# backplane.net
KiCad netlist of a schematic drawn in EAGLE
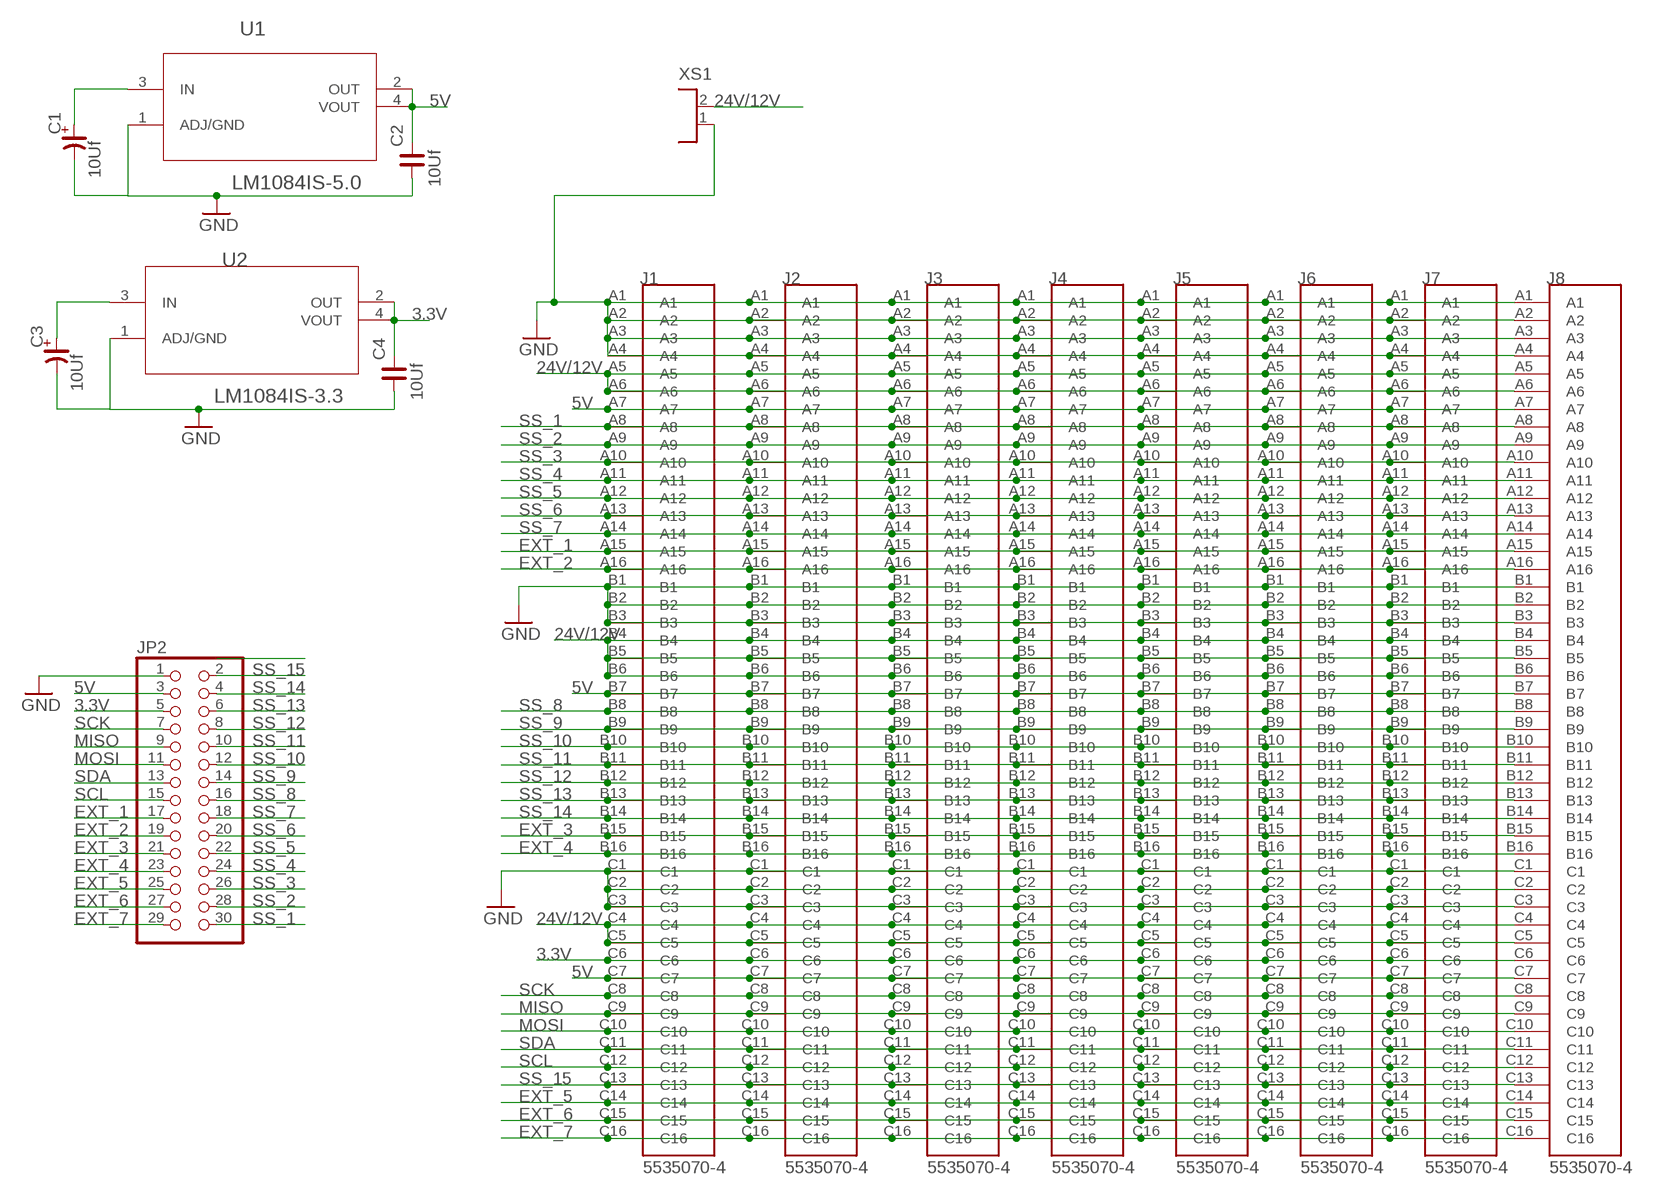
[diagram p0: schematic, sheet 1]

(export (version "E")
  (design (tool "Eeschema 10.0.6"))
  (components
    (comp (ref "C1")
      (value "10Uf")
      (footprint "eagle-import:C3216_T")
      (libsource (lib "eagle-import") (part "CP_3216"))
    )
    (comp (ref "C2")
      (value "10Uf")
      (footprint "eagle-import:C1206")
      (libsource (lib "eagle-import") (part "C_1206"))
    )
    (comp (ref "C3")
      (value "10Uf")
      (footprint "eagle-import:C3216_T")
      (libsource (lib "eagle-import") (part "CP_3216"))
    )
    (comp (ref "C4")
      (value "10Uf")
      (footprint "eagle-import:C1206")
      (libsource (lib "eagle-import") (part "C_1206"))
    )
    (comp (ref "J1")
      (value "5535070-4")
      (footprint "eagle-import:TE_5535070-4")
      (fields (field (name "MF") "TE Connectivity"))
      (libsource (lib "eagle-import") (part "5535070-4"))
    )
    (comp (ref "J2")
      (value "5535070-4")
      (footprint "eagle-import:TE_5535070-4")
      (fields (field (name "MF") "TE Connectivity"))
      (libsource (lib "eagle-import") (part "5535070-4"))
    )
    (comp (ref "J3")
      (value "5535070-4")
      (footprint "eagle-import:TE_5535070-4")
      (fields (field (name "MF") "TE Connectivity"))
      (libsource (lib "eagle-import") (part "5535070-4"))
    )
    (comp (ref "J4")
      (value "5535070-4")
      (footprint "eagle-import:TE_5535070-4")
      (fields (field (name "MF") "TE Connectivity"))
      (libsource (lib "eagle-import") (part "5535070-4"))
    )
    (comp (ref "J5")
      (value "5535070-4")
      (footprint "eagle-import:TE_5535070-4")
      (fields (field (name "MF") "TE Connectivity"))
      (libsource (lib "eagle-import") (part "5535070-4"))
    )
    (comp (ref "J6")
      (value "5535070-4")
      (footprint "eagle-import:TE_5535070-4")
      (fields (field (name "MF") "TE Connectivity"))
      (libsource (lib "eagle-import") (part "5535070-4"))
    )
    (comp (ref "J7")
      (value "5535070-4")
      (footprint "eagle-import:TE_5535070-4")
      (fields (field (name "MF") "TE Connectivity"))
      (libsource (lib "eagle-import") (part "5535070-4"))
    )
    (comp (ref "J8")
      (value "5535070-4")
      (footprint "eagle-import:TE_5535070-4")
      (fields (field (name "MF") "TE Connectivity"))
      (libsource (lib "eagle-import") (part "5535070-4"))
    )
    (comp (ref "JP2")
      (value "PINHD-2X15")
      (footprint "eagle-import:2X15")
      (libsource (lib "eagle-import") (part "PINHD-2X15"))
    )
    (comp (ref "U1")
      (value "LM1084IS-5.0")
      (footprint "eagle-import:TO254P1435X457-3N")
      (fields (field (name "MF") "Texas Instruments"))
      (libsource (lib "eagle-import") (part "LM1084IS-5.0"))
    )
    (comp (ref "U2")
      (value "LM1084IS-3.3")
      (footprint "eagle-import:TO254P1435X457-3N")
      (fields (field (name "MF") "Texas Instruments") (field (name "MP") "LM1084IS-5.0"))
      (libsource (lib "eagle-import") (part "LM1084IS-5.0"))
    )
    (comp (ref "XS1")
      (value "2P")
      (footprint "eagle-import:DG55CB-2P-1")
      (libsource (lib "eagle-import") (part "2P"))
    )
  )
  (nets
    (net (code "1") (name "/3.3V") (class "Default")
      (node (ref "C4") (pin "2") (pinfunction "2_2") (pintype "passive"))
      (node (ref "J1") (pin "C6") (pinfunction "C6_C6") (pintype "passive"))
      (node (ref "J2") (pin "C6") (pinfunction "C6_C6") (pintype "passive"))
      (node (ref "J3") (pin "C6") (pinfunction "C6_C6") (pintype "passive"))
      (node (ref "J4") (pin "C6") (pinfunction "C6_C6") (pintype "passive"))
      (node (ref "J5") (pin "C6") (pinfunction "C6_C6") (pintype "passive"))
      (node (ref "J6") (pin "C6") (pinfunction "C6_C6") (pintype "passive"))
      (node (ref "J7") (pin "C6") (pinfunction "C6_C6") (pintype "passive"))
      (node (ref "J8") (pin "C6") (pinfunction "C6_C6") (pintype "passive"))
      (node (ref "JP2") (pin "5") (pinfunction "5_5") (pintype "passive"))
      (node (ref "U2") (pin "2") (pinfunction "OUT_2") (pintype "output"))
      (node (ref "U2") (pin "4") (pinfunction "VOUT_4") (pintype "output"))
    )
    (net (code "2") (name "/5V") (class "Default")
      (node (ref "C2") (pin "2") (pinfunction "2_2") (pintype "passive"))
      (node (ref "J1") (pin "A7") (pinfunction "A7_A7") (pintype "passive"))
      (node (ref "J1") (pin "B7") (pinfunction "B7_B7") (pintype "passive"))
      (node (ref "J1") (pin "C7") (pinfunction "C7_C7") (pintype "passive"))
      (node (ref "J2") (pin "A7") (pinfunction "A7_A7") (pintype "passive"))
      (node (ref "J2") (pin "B7") (pinfunction "B7_B7") (pintype "passive"))
      (node (ref "J2") (pin "C7") (pinfunction "C7_C7") (pintype "passive"))
      (node (ref "J3") (pin "A7") (pinfunction "A7_A7") (pintype "passive"))
      (node (ref "J3") (pin "B7") (pinfunction "B7_B7") (pintype "passive"))
      (node (ref "J3") (pin "C7") (pinfunction "C7_C7") (pintype "passive"))
      (node (ref "J4") (pin "A7") (pinfunction "A7_A7") (pintype "passive"))
      (node (ref "J4") (pin "B7") (pinfunction "B7_B7") (pintype "passive"))
      (node (ref "J4") (pin "C7") (pinfunction "C7_C7") (pintype "passive"))
      (node (ref "J5") (pin "A7") (pinfunction "A7_A7") (pintype "passive"))
      (node (ref "J5") (pin "B7") (pinfunction "B7_B7") (pintype "passive"))
      (node (ref "J5") (pin "C7") (pinfunction "C7_C7") (pintype "passive"))
      (node (ref "J6") (pin "A7") (pinfunction "A7_A7") (pintype "passive"))
      (node (ref "J6") (pin "B7") (pinfunction "B7_B7") (pintype "passive"))
      (node (ref "J6") (pin "C7") (pinfunction "C7_C7") (pintype "passive"))
      (node (ref "J7") (pin "A7") (pinfunction "A7_A7") (pintype "passive"))
      (node (ref "J7") (pin "B7") (pinfunction "B7_B7") (pintype "passive"))
      (node (ref "J7") (pin "C7") (pinfunction "C7_C7") (pintype "passive"))
      (node (ref "J8") (pin "A7") (pinfunction "A7_A7") (pintype "passive"))
      (node (ref "J8") (pin "B7") (pinfunction "B7_B7") (pintype "passive"))
      (node (ref "J8") (pin "C7") (pinfunction "C7_C7") (pintype "passive"))
      (node (ref "JP2") (pin "3") (pinfunction "3_3") (pintype "passive"))
      (node (ref "U1") (pin "2") (pinfunction "OUT_2") (pintype "output"))
      (node (ref "U1") (pin "4") (pinfunction "VOUT_4") (pintype "output"))
    )
    (net (code "3") (name "/24V{slash}12V") (class "Default")
      (node (ref "J1") (pin "A5") (pinfunction "A5_A5") (pintype "passive"))
      (node (ref "J1") (pin "A6") (pinfunction "A6_A6") (pintype "passive"))
      (node (ref "J1") (pin "B4") (pinfunction "B4_B4") (pintype "passive"))
      (node (ref "J1") (pin "B5") (pinfunction "B5_B5") (pintype "passive"))
      (node (ref "J1") (pin "B6") (pinfunction "B6_B6") (pintype "passive"))
      (node (ref "J1") (pin "C4") (pinfunction "C4_C4") (pintype "passive"))
      (node (ref "J1") (pin "C5") (pinfunction "C5_C5") (pintype "passive"))
      (node (ref "J2") (pin "A5") (pinfunction "A5_A5") (pintype "passive"))
      (node (ref "J2") (pin "A6") (pinfunction "A6_A6") (pintype "passive"))
      (node (ref "J2") (pin "B4") (pinfunction "B4_B4") (pintype "passive"))
      (node (ref "J2") (pin "B5") (pinfunction "B5_B5") (pintype "passive"))
      (node (ref "J2") (pin "B6") (pinfunction "B6_B6") (pintype "passive"))
      (node (ref "J2") (pin "C4") (pinfunction "C4_C4") (pintype "passive"))
      (node (ref "J2") (pin "C5") (pinfunction "C5_C5") (pintype "passive"))
      (node (ref "J3") (pin "A5") (pinfunction "A5_A5") (pintype "passive"))
      (node (ref "J3") (pin "A6") (pinfunction "A6_A6") (pintype "passive"))
      (node (ref "J3") (pin "B4") (pinfunction "B4_B4") (pintype "passive"))
      (node (ref "J3") (pin "B5") (pinfunction "B5_B5") (pintype "passive"))
      (node (ref "J3") (pin "B6") (pinfunction "B6_B6") (pintype "passive"))
      (node (ref "J3") (pin "C4") (pinfunction "C4_C4") (pintype "passive"))
      (node (ref "J3") (pin "C5") (pinfunction "C5_C5") (pintype "passive"))
      (node (ref "J4") (pin "A5") (pinfunction "A5_A5") (pintype "passive"))
      (node (ref "J4") (pin "A6") (pinfunction "A6_A6") (pintype "passive"))
      (node (ref "J4") (pin "B4") (pinfunction "B4_B4") (pintype "passive"))
      (node (ref "J4") (pin "B5") (pinfunction "B5_B5") (pintype "passive"))
      (node (ref "J4") (pin "B6") (pinfunction "B6_B6") (pintype "passive"))
      (node (ref "J4") (pin "C4") (pinfunction "C4_C4") (pintype "passive"))
      (node (ref "J4") (pin "C5") (pinfunction "C5_C5") (pintype "passive"))
      (node (ref "J5") (pin "A5") (pinfunction "A5_A5") (pintype "passive"))
      (node (ref "J5") (pin "A6") (pinfunction "A6_A6") (pintype "passive"))
      (node (ref "J5") (pin "B4") (pinfunction "B4_B4") (pintype "passive"))
      (node (ref "J5") (pin "B5") (pinfunction "B5_B5") (pintype "passive"))
      (node (ref "J5") (pin "B6") (pinfunction "B6_B6") (pintype "passive"))
      (node (ref "J5") (pin "C4") (pinfunction "C4_C4") (pintype "passive"))
      (node (ref "J5") (pin "C5") (pinfunction "C5_C5") (pintype "passive"))
      (node (ref "J6") (pin "A5") (pinfunction "A5_A5") (pintype "passive"))
      (node (ref "J6") (pin "A6") (pinfunction "A6_A6") (pintype "passive"))
      (node (ref "J6") (pin "B4") (pinfunction "B4_B4") (pintype "passive"))
      (node (ref "J6") (pin "B5") (pinfunction "B5_B5") (pintype "passive"))
      (node (ref "J6") (pin "B6") (pinfunction "B6_B6") (pintype "passive"))
      (node (ref "J6") (pin "C4") (pinfunction "C4_C4") (pintype "passive"))
      (node (ref "J6") (pin "C5") (pinfunction "C5_C5") (pintype "passive"))
      (node (ref "J7") (pin "A5") (pinfunction "A5_A5") (pintype "passive"))
      (node (ref "J7") (pin "A6") (pinfunction "A6_A6") (pintype "passive"))
      (node (ref "J7") (pin "B4") (pinfunction "B4_B4") (pintype "passive"))
      (node (ref "J7") (pin "B5") (pinfunction "B5_B5") (pintype "passive"))
      (node (ref "J7") (pin "B6") (pinfunction "B6_B6") (pintype "passive"))
      (node (ref "J7") (pin "C4") (pinfunction "C4_C4") (pintype "passive"))
      (node (ref "J7") (pin "C5") (pinfunction "C5_C5") (pintype "passive"))
      (node (ref "J8") (pin "A5") (pinfunction "A5_A5") (pintype "passive"))
      (node (ref "J8") (pin "A6") (pinfunction "A6_A6") (pintype "passive"))
      (node (ref "J8") (pin "B4") (pinfunction "B4_B4") (pintype "passive"))
      (node (ref "J8") (pin "B5") (pinfunction "B5_B5") (pintype "passive"))
      (node (ref "J8") (pin "B6") (pinfunction "B6_B6") (pintype "passive"))
      (node (ref "J8") (pin "C4") (pinfunction "C4_C4") (pintype "passive"))
      (node (ref "J8") (pin "C5") (pinfunction "C5_C5") (pintype "passive"))
      (node (ref "XS1") (pin "2") (pinfunction "P$2_2") (pintype "bidirectional"))
    )
    (net (code "4") (name "/EXT_1") (class "Default")
      (node (ref "J1") (pin "A15") (pinfunction "A15_A15") (pintype "passive"))
      (node (ref "J2") (pin "A15") (pinfunction "A15_A15") (pintype "passive"))
      (node (ref "J3") (pin "A15") (pinfunction "A15_A15") (pintype "passive"))
      (node (ref "J4") (pin "A15") (pinfunction "A15_A15") (pintype "passive"))
      (node (ref "J5") (pin "A15") (pinfunction "A15_A15") (pintype "passive"))
      (node (ref "J6") (pin "A15") (pinfunction "A15_A15") (pintype "passive"))
      (node (ref "J7") (pin "A15") (pinfunction "A15_A15") (pintype "passive"))
      (node (ref "J8") (pin "A15") (pinfunction "A15_A15") (pintype "passive"))
      (node (ref "JP2") (pin "17") (pinfunction "17_17") (pintype "passive"))
    )
    (net (code "5") (name "/EXT_2") (class "Default")
      (node (ref "J1") (pin "A16") (pinfunction "A16_A16") (pintype "passive"))
      (node (ref "J2") (pin "A16") (pinfunction "A16_A16") (pintype "passive"))
      (node (ref "J3") (pin "A16") (pinfunction "A16_A16") (pintype "passive"))
      (node (ref "J4") (pin "A16") (pinfunction "A16_A16") (pintype "passive"))
      (node (ref "J5") (pin "A16") (pinfunction "A16_A16") (pintype "passive"))
      (node (ref "J6") (pin "A16") (pinfunction "A16_A16") (pintype "passive"))
      (node (ref "J7") (pin "A16") (pinfunction "A16_A16") (pintype "passive"))
      (node (ref "J8") (pin "A16") (pinfunction "A16_A16") (pintype "passive"))
      (node (ref "JP2") (pin "19") (pinfunction "19_19") (pintype "passive"))
    )
    (net (code "6") (name "/EXT_3") (class "Default")
      (node (ref "J1") (pin "B15") (pinfunction "B15_B15") (pintype "passive"))
      (node (ref "J2") (pin "B15") (pinfunction "B15_B15") (pintype "passive"))
      (node (ref "J3") (pin "B15") (pinfunction "B15_B15") (pintype "passive"))
      (node (ref "J4") (pin "B15") (pinfunction "B15_B15") (pintype "passive"))
      (node (ref "J5") (pin "B15") (pinfunction "B15_B15") (pintype "passive"))
      (node (ref "J6") (pin "B15") (pinfunction "B15_B15") (pintype "passive"))
      (node (ref "J7") (pin "B15") (pinfunction "B15_B15") (pintype "passive"))
      (node (ref "J8") (pin "B15") (pinfunction "B15_B15") (pintype "passive"))
      (node (ref "JP2") (pin "21") (pinfunction "21_21") (pintype "passive"))
    )
    (net (code "7") (name "/EXT_4") (class "Default")
      (node (ref "J1") (pin "B16") (pinfunction "B16_B16") (pintype "passive"))
      (node (ref "J2") (pin "B16") (pinfunction "B16_B16") (pintype "passive"))
      (node (ref "J3") (pin "B16") (pinfunction "B16_B16") (pintype "passive"))
      (node (ref "J4") (pin "B16") (pinfunction "B16_B16") (pintype "passive"))
      (node (ref "J5") (pin "B16") (pinfunction "B16_B16") (pintype "passive"))
      (node (ref "J6") (pin "B16") (pinfunction "B16_B16") (pintype "passive"))
      (node (ref "J7") (pin "B16") (pinfunction "B16_B16") (pintype "passive"))
      (node (ref "J8") (pin "B16") (pinfunction "B16_B16") (pintype "passive"))
      (node (ref "JP2") (pin "23") (pinfunction "23_23") (pintype "passive"))
    )
    (net (code "8") (name "/EXT_5") (class "Default")
      (node (ref "J1") (pin "C14") (pinfunction "C14_C14") (pintype "passive"))
      (node (ref "J2") (pin "C14") (pinfunction "C14_C14") (pintype "passive"))
      (node (ref "J3") (pin "C14") (pinfunction "C14_C14") (pintype "passive"))
      (node (ref "J4") (pin "C14") (pinfunction "C14_C14") (pintype "passive"))
      (node (ref "J5") (pin "C14") (pinfunction "C14_C14") (pintype "passive"))
      (node (ref "J6") (pin "C14") (pinfunction "C14_C14") (pintype "passive"))
      (node (ref "J7") (pin "C14") (pinfunction "C14_C14") (pintype "passive"))
      (node (ref "J8") (pin "C14") (pinfunction "C14_C14") (pintype "passive"))
      (node (ref "JP2") (pin "25") (pinfunction "25_25") (pintype "passive"))
    )
    (net (code "9") (name "/EXT_6") (class "Default")
      (node (ref "J1") (pin "C15") (pinfunction "C15_C15") (pintype "passive"))
      (node (ref "J2") (pin "C15") (pinfunction "C15_C15") (pintype "passive"))
      (node (ref "J3") (pin "C15") (pinfunction "C15_C15") (pintype "passive"))
      (node (ref "J4") (pin "C15") (pinfunction "C15_C15") (pintype "passive"))
      (node (ref "J5") (pin "C15") (pinfunction "C15_C15") (pintype "passive"))
      (node (ref "J6") (pin "C15") (pinfunction "C15_C15") (pintype "passive"))
      (node (ref "J7") (pin "C15") (pinfunction "C15_C15") (pintype "passive"))
      (node (ref "J8") (pin "C15") (pinfunction "C15_C15") (pintype "passive"))
      (node (ref "JP2") (pin "27") (pinfunction "27_27") (pintype "passive"))
    )
    (net (code "10") (name "/EXT_7") (class "Default")
      (node (ref "J1") (pin "C16") (pinfunction "C16_C16") (pintype "passive"))
      (node (ref "J2") (pin "C16") (pinfunction "C16_C16") (pintype "passive"))
      (node (ref "J3") (pin "C16") (pinfunction "C16_C16") (pintype "passive"))
      (node (ref "J4") (pin "C16") (pinfunction "C16_C16") (pintype "passive"))
      (node (ref "J5") (pin "C16") (pinfunction "C16_C16") (pintype "passive"))
      (node (ref "J6") (pin "C16") (pinfunction "C16_C16") (pintype "passive"))
      (node (ref "J7") (pin "C16") (pinfunction "C16_C16") (pintype "passive"))
      (node (ref "J8") (pin "C16") (pinfunction "C16_C16") (pintype "passive"))
      (node (ref "JP2") (pin "29") (pinfunction "29_29") (pintype "passive"))
    )
    (net (code "11") (name "/MISO") (class "Default")
      (node (ref "J1") (pin "C9") (pinfunction "C9_C9") (pintype "passive"))
      (node (ref "J2") (pin "C9") (pinfunction "C9_C9") (pintype "passive"))
      (node (ref "J3") (pin "C9") (pinfunction "C9_C9") (pintype "passive"))
      (node (ref "J4") (pin "C9") (pinfunction "C9_C9") (pintype "passive"))
      (node (ref "J5") (pin "C9") (pinfunction "C9_C9") (pintype "passive"))
      (node (ref "J6") (pin "C9") (pinfunction "C9_C9") (pintype "passive"))
      (node (ref "J7") (pin "C9") (pinfunction "C9_C9") (pintype "passive"))
      (node (ref "J8") (pin "C9") (pinfunction "C9_C9") (pintype "passive"))
      (node (ref "JP2") (pin "9") (pinfunction "9_9") (pintype "passive"))
    )
    (net (code "12") (name "/MOSI") (class "Default")
      (node (ref "J1") (pin "C10") (pinfunction "C10_C10") (pintype "passive"))
      (node (ref "J2") (pin "C10") (pinfunction "C10_C10") (pintype "passive"))
      (node (ref "J3") (pin "C10") (pinfunction "C10_C10") (pintype "passive"))
      (node (ref "J4") (pin "C10") (pinfunction "C10_C10") (pintype "passive"))
      (node (ref "J5") (pin "C10") (pinfunction "C10_C10") (pintype "passive"))
      (node (ref "J6") (pin "C10") (pinfunction "C10_C10") (pintype "passive"))
      (node (ref "J7") (pin "C10") (pinfunction "C10_C10") (pintype "passive"))
      (node (ref "J8") (pin "C10") (pinfunction "C10_C10") (pintype "passive"))
      (node (ref "JP2") (pin "11") (pinfunction "11_11") (pintype "passive"))
    )
    (net (code "13") (name "/SCK") (class "Default")
      (node (ref "J1") (pin "C8") (pinfunction "C8_C8") (pintype "passive"))
      (node (ref "J2") (pin "C8") (pinfunction "C8_C8") (pintype "passive"))
      (node (ref "J3") (pin "C8") (pinfunction "C8_C8") (pintype "passive"))
      (node (ref "J4") (pin "C8") (pinfunction "C8_C8") (pintype "passive"))
      (node (ref "J5") (pin "C8") (pinfunction "C8_C8") (pintype "passive"))
      (node (ref "J6") (pin "C8") (pinfunction "C8_C8") (pintype "passive"))
      (node (ref "J7") (pin "C8") (pinfunction "C8_C8") (pintype "passive"))
      (node (ref "J8") (pin "C8") (pinfunction "C8_C8") (pintype "passive"))
      (node (ref "JP2") (pin "7") (pinfunction "7_7") (pintype "passive"))
    )
    (net (code "14") (name "/SCL") (class "Default")
      (node (ref "J1") (pin "C12") (pinfunction "C12_C12") (pintype "passive"))
      (node (ref "J2") (pin "C12") (pinfunction "C12_C12") (pintype "passive"))
      (node (ref "J3") (pin "C12") (pinfunction "C12_C12") (pintype "passive"))
      (node (ref "J4") (pin "C12") (pinfunction "C12_C12") (pintype "passive"))
      (node (ref "J5") (pin "C12") (pinfunction "C12_C12") (pintype "passive"))
      (node (ref "J6") (pin "C12") (pinfunction "C12_C12") (pintype "passive"))
      (node (ref "J7") (pin "C12") (pinfunction "C12_C12") (pintype "passive"))
      (node (ref "J8") (pin "C12") (pinfunction "C12_C12") (pintype "passive"))
      (node (ref "JP2") (pin "15") (pinfunction "15_15") (pintype "passive"))
    )
    (net (code "15") (name "/SDA") (class "Default")
      (node (ref "J1") (pin "C11") (pinfunction "C11_C11") (pintype "passive"))
      (node (ref "J2") (pin "C11") (pinfunction "C11_C11") (pintype "passive"))
      (node (ref "J3") (pin "C11") (pinfunction "C11_C11") (pintype "passive"))
      (node (ref "J4") (pin "C11") (pinfunction "C11_C11") (pintype "passive"))
      (node (ref "J5") (pin "C11") (pinfunction "C11_C11") (pintype "passive"))
      (node (ref "J6") (pin "C11") (pinfunction "C11_C11") (pintype "passive"))
      (node (ref "J7") (pin "C11") (pinfunction "C11_C11") (pintype "passive"))
      (node (ref "J8") (pin "C11") (pinfunction "C11_C11") (pintype "passive"))
      (node (ref "JP2") (pin "13") (pinfunction "13_13") (pintype "passive"))
    )
    (net (code "16") (name "/SS_1") (class "Default")
      (node (ref "J1") (pin "A8") (pinfunction "A8_A8") (pintype "passive"))
      (node (ref "J2") (pin "A8") (pinfunction "A8_A8") (pintype "passive"))
      (node (ref "J3") (pin "A8") (pinfunction "A8_A8") (pintype "passive"))
      (node (ref "J4") (pin "A8") (pinfunction "A8_A8") (pintype "passive"))
      (node (ref "J5") (pin "A8") (pinfunction "A8_A8") (pintype "passive"))
      (node (ref "J6") (pin "A8") (pinfunction "A8_A8") (pintype "passive"))
      (node (ref "J7") (pin "A8") (pinfunction "A8_A8") (pintype "passive"))
      (node (ref "J8") (pin "A8") (pinfunction "A8_A8") (pintype "passive"))
      (node (ref "JP2") (pin "30") (pinfunction "30_30") (pintype "passive"))
    )
    (net (code "17") (name "/SS_2") (class "Default")
      (node (ref "J1") (pin "A9") (pinfunction "A9_A9") (pintype "passive"))
      (node (ref "J2") (pin "A9") (pinfunction "A9_A9") (pintype "passive"))
      (node (ref "J3") (pin "A9") (pinfunction "A9_A9") (pintype "passive"))
      (node (ref "J4") (pin "A9") (pinfunction "A9_A9") (pintype "passive"))
      (node (ref "J5") (pin "A9") (pinfunction "A9_A9") (pintype "passive"))
      (node (ref "J6") (pin "A9") (pinfunction "A9_A9") (pintype "passive"))
      (node (ref "J7") (pin "A9") (pinfunction "A9_A9") (pintype "passive"))
      (node (ref "J8") (pin "A9") (pinfunction "A9_A9") (pintype "passive"))
      (node (ref "JP2") (pin "28") (pinfunction "28_28") (pintype "passive"))
    )
    (net (code "18") (name "/SS_3") (class "Default")
      (node (ref "J1") (pin "A10") (pinfunction "A10_A10") (pintype "passive"))
      (node (ref "J2") (pin "A10") (pinfunction "A10_A10") (pintype "passive"))
      (node (ref "J3") (pin "A10") (pinfunction "A10_A10") (pintype "passive"))
      (node (ref "J4") (pin "A10") (pinfunction "A10_A10") (pintype "passive"))
      (node (ref "J5") (pin "A10") (pinfunction "A10_A10") (pintype "passive"))
      (node (ref "J6") (pin "A10") (pinfunction "A10_A10") (pintype "passive"))
      (node (ref "J7") (pin "A10") (pinfunction "A10_A10") (pintype "passive"))
      (node (ref "J8") (pin "A10") (pinfunction "A10_A10") (pintype "passive"))
      (node (ref "JP2") (pin "26") (pinfunction "26_26") (pintype "passive"))
    )
    (net (code "19") (name "/SS_4") (class "Default")
      (node (ref "J1") (pin "A11") (pinfunction "A11_A11") (pintype "passive"))
      (node (ref "J2") (pin "A11") (pinfunction "A11_A11") (pintype "passive"))
      (node (ref "J3") (pin "A11") (pinfunction "A11_A11") (pintype "passive"))
      (node (ref "J4") (pin "A11") (pinfunction "A11_A11") (pintype "passive"))
      (node (ref "J5") (pin "A11") (pinfunction "A11_A11") (pintype "passive"))
      (node (ref "J6") (pin "A11") (pinfunction "A11_A11") (pintype "passive"))
      (node (ref "J7") (pin "A11") (pinfunction "A11_A11") (pintype "passive"))
      (node (ref "J8") (pin "A11") (pinfunction "A11_A11") (pintype "passive"))
      (node (ref "JP2") (pin "24") (pinfunction "24_24") (pintype "passive"))
    )
    (net (code "20") (name "/SS_5") (class "Default")
      (node (ref "J1") (pin "A12") (pinfunction "A12_A12") (pintype "passive"))
      (node (ref "J2") (pin "A12") (pinfunction "A12_A12") (pintype "passive"))
      (node (ref "J3") (pin "A12") (pinfunction "A12_A12") (pintype "passive"))
      (node (ref "J4") (pin "A12") (pinfunction "A12_A12") (pintype "passive"))
      (node (ref "J5") (pin "A12") (pinfunction "A12_A12") (pintype "passive"))
      (node (ref "J6") (pin "A12") (pinfunction "A12_A12") (pintype "passive"))
      (node (ref "J7") (pin "A12") (pinfunction "A12_A12") (pintype "passive"))
      (node (ref "J8") (pin "A12") (pinfunction "A12_A12") (pintype "passive"))
      (node (ref "JP2") (pin "22") (pinfunction "22_22") (pintype "passive"))
    )
    (net (code "21") (name "/SS_6") (class "Default")
      (node (ref "J1") (pin "A13") (pinfunction "A13_A13") (pintype "passive"))
      (node (ref "J2") (pin "A13") (pinfunction "A13_A13") (pintype "passive"))
      (node (ref "J3") (pin "A13") (pinfunction "A13_A13") (pintype "passive"))
      (node (ref "J4") (pin "A13") (pinfunction "A13_A13") (pintype "passive"))
      (node (ref "J5") (pin "A13") (pinfunction "A13_A13") (pintype "passive"))
      (node (ref "J6") (pin "A13") (pinfunction "A13_A13") (pintype "passive"))
      (node (ref "J7") (pin "A13") (pinfunction "A13_A13") (pintype "passive"))
      (node (ref "J8") (pin "A13") (pinfunction "A13_A13") (pintype "passive"))
      (node (ref "JP2") (pin "20") (pinfunction "20_20") (pintype "passive"))
    )
    (net (code "22") (name "/SS_7") (class "Default")
      (node (ref "J1") (pin "A14") (pinfunction "A14_A14") (pintype "passive"))
      (node (ref "J2") (pin "A14") (pinfunction "A14_A14") (pintype "passive"))
      (node (ref "J3") (pin "A14") (pinfunction "A14_A14") (pintype "passive"))
      (node (ref "J4") (pin "A14") (pinfunction "A14_A14") (pintype "passive"))
      (node (ref "J5") (pin "A14") (pinfunction "A14_A14") (pintype "passive"))
      (node (ref "J6") (pin "A14") (pinfunction "A14_A14") (pintype "passive"))
      (node (ref "J7") (pin "A14") (pinfunction "A14_A14") (pintype "passive"))
      (node (ref "J8") (pin "A14") (pinfunction "A14_A14") (pintype "passive"))
      (node (ref "JP2") (pin "18") (pinfunction "18_18") (pintype "passive"))
    )
    (net (code "23") (name "/SS_8") (class "Default")
      (node (ref "J1") (pin "B8") (pinfunction "B8_B8") (pintype "passive"))
      (node (ref "J2") (pin "B8") (pinfunction "B8_B8") (pintype "passive"))
      (node (ref "J3") (pin "B8") (pinfunction "B8_B8") (pintype "passive"))
      (node (ref "J4") (pin "B8") (pinfunction "B8_B8") (pintype "passive"))
      (node (ref "J5") (pin "B8") (pinfunction "B8_B8") (pintype "passive"))
      (node (ref "J6") (pin "B8") (pinfunction "B8_B8") (pintype "passive"))
      (node (ref "J7") (pin "B8") (pinfunction "B8_B8") (pintype "passive"))
      (node (ref "J8") (pin "B8") (pinfunction "B8_B8") (pintype "passive"))
      (node (ref "JP2") (pin "16") (pinfunction "16_16") (pintype "passive"))
    )
    (net (code "24") (name "/SS_9") (class "Default")
      (node (ref "J1") (pin "B9") (pinfunction "B9_B9") (pintype "passive"))
      (node (ref "J2") (pin "B9") (pinfunction "B9_B9") (pintype "passive"))
      (node (ref "J3") (pin "B9") (pinfunction "B9_B9") (pintype "passive"))
      (node (ref "J4") (pin "B9") (pinfunction "B9_B9") (pintype "passive"))
      (node (ref "J5") (pin "B9") (pinfunction "B9_B9") (pintype "passive"))
      (node (ref "J6") (pin "B9") (pinfunction "B9_B9") (pintype "passive"))
      (node (ref "J7") (pin "B9") (pinfunction "B9_B9") (pintype "passive"))
      (node (ref "J8") (pin "B9") (pinfunction "B9_B9") (pintype "passive"))
      (node (ref "JP2") (pin "14") (pinfunction "14_14") (pintype "passive"))
    )
    (net (code "25") (name "/SS_10") (class "Default")
      (node (ref "J1") (pin "B10") (pinfunction "B10_B10") (pintype "passive"))
      (node (ref "J2") (pin "B10") (pinfunction "B10_B10") (pintype "passive"))
      (node (ref "J3") (pin "B10") (pinfunction "B10_B10") (pintype "passive"))
      (node (ref "J4") (pin "B10") (pinfunction "B10_B10") (pintype "passive"))
      (node (ref "J5") (pin "B10") (pinfunction "B10_B10") (pintype "passive"))
      (node (ref "J6") (pin "B10") (pinfunction "B10_B10") (pintype "passive"))
      (node (ref "J7") (pin "B10") (pinfunction "B10_B10") (pintype "passive"))
      (node (ref "J8") (pin "B10") (pinfunction "B10_B10") (pintype "passive"))
      (node (ref "JP2") (pin "12") (pinfunction "12_12") (pintype "passive"))
    )
    (net (code "26") (name "/SS_11") (class "Default")
      (node (ref "J1") (pin "B11") (pinfunction "B11_B11") (pintype "passive"))
      (node (ref "J2") (pin "B11") (pinfunction "B11_B11") (pintype "passive"))
      (node (ref "J3") (pin "B11") (pinfunction "B11_B11") (pintype "passive"))
      (node (ref "J4") (pin "B11") (pinfunction "B11_B11") (pintype "passive"))
      (node (ref "J5") (pin "B11") (pinfunction "B11_B11") (pintype "passive"))
      (node (ref "J6") (pin "B11") (pinfunction "B11_B11") (pintype "passive"))
      (node (ref "J7") (pin "B11") (pinfunction "B11_B11") (pintype "passive"))
      (node (ref "J8") (pin "B11") (pinfunction "B11_B11") (pintype "passive"))
      (node (ref "JP2") (pin "10") (pinfunction "10_10") (pintype "passive"))
    )
    (net (code "27") (name "/SS_12") (class "Default")
      (node (ref "J1") (pin "B12") (pinfunction "B12_B12") (pintype "passive"))
      (node (ref "J2") (pin "B12") (pinfunction "B12_B12") (pintype "passive"))
      (node (ref "J3") (pin "B12") (pinfunction "B12_B12") (pintype "passive"))
      (node (ref "J4") (pin "B12") (pinfunction "B12_B12") (pintype "passive"))
      (node (ref "J5") (pin "B12") (pinfunction "B12_B12") (pintype "passive"))
      (node (ref "J6") (pin "B12") (pinfunction "B12_B12") (pintype "passive"))
      (node (ref "J7") (pin "B12") (pinfunction "B12_B12") (pintype "passive"))
      (node (ref "J8") (pin "B12") (pinfunction "B12_B12") (pintype "passive"))
      (node (ref "JP2") (pin "8") (pinfunction "8_8") (pintype "passive"))
    )
    (net (code "28") (name "/SS_13") (class "Default")
      (node (ref "J1") (pin "B13") (pinfunction "B13_B13") (pintype "passive"))
      (node (ref "J2") (pin "B13") (pinfunction "B13_B13") (pintype "passive"))
      (node (ref "J3") (pin "B13") (pinfunction "B13_B13") (pintype "passive"))
      (node (ref "J4") (pin "B13") (pinfunction "B13_B13") (pintype "passive"))
      (node (ref "J5") (pin "B13") (pinfunction "B13_B13") (pintype "passive"))
      (node (ref "J6") (pin "B13") (pinfunction "B13_B13") (pintype "passive"))
      (node (ref "J7") (pin "B13") (pinfunction "B13_B13") (pintype "passive"))
      (node (ref "J8") (pin "B13") (pinfunction "B13_B13") (pintype "passive"))
      (node (ref "JP2") (pin "6") (pinfunction "6_6") (pintype "passive"))
    )
    (net (code "29") (name "/SS_14") (class "Default")
      (node (ref "J1") (pin "B14") (pinfunction "B14_B14") (pintype "passive"))
      (node (ref "J2") (pin "B14") (pinfunction "B14_B14") (pintype "passive"))
      (node (ref "J3") (pin "B14") (pinfunction "B14_B14") (pintype "passive"))
      (node (ref "J4") (pin "B14") (pinfunction "B14_B14") (pintype "passive"))
      (node (ref "J5") (pin "B14") (pinfunction "B14_B14") (pintype "passive"))
      (node (ref "J6") (pin "B14") (pinfunction "B14_B14") (pintype "passive"))
      (node (ref "J7") (pin "B14") (pinfunction "B14_B14") (pintype "passive"))
      (node (ref "J8") (pin "B14") (pinfunction "B14_B14") (pintype "passive"))
      (node (ref "JP2") (pin "4") (pinfunction "4_4") (pintype "passive"))
    )
    (net (code "30") (name "/SS_15") (class "Default")
      (node (ref "J1") (pin "C13") (pinfunction "C13_C13") (pintype "passive"))
      (node (ref "J2") (pin "C13") (pinfunction "C13_C13") (pintype "passive"))
      (node (ref "J3") (pin "C13") (pinfunction "C13_C13") (pintype "passive"))
      (node (ref "J4") (pin "C13") (pinfunction "C13_C13") (pintype "passive"))
      (node (ref "J5") (pin "C13") (pinfunction "C13_C13") (pintype "passive"))
      (node (ref "J6") (pin "C13") (pinfunction "C13_C13") (pintype "passive"))
      (node (ref "J7") (pin "C13") (pinfunction "C13_C13") (pintype "passive"))
      (node (ref "J8") (pin "C13") (pinfunction "C13_C13") (pintype "passive"))
      (node (ref "JP2") (pin "2") (pinfunction "2_2") (pintype "passive"))
    )
    (net (code "31") (name "GND") (class "Default")
      (node (ref "C1") (pin "-") (pinfunction "-_-") (pintype "passive"))
      (node (ref "C2") (pin "1") (pinfunction "1_1") (pintype "passive"))
      (node (ref "C3") (pin "-") (pinfunction "-_-") (pintype "passive"))
      (node (ref "C4") (pin "1") (pinfunction "1_1") (pintype "passive"))
      (node (ref "J1") (pin "A1") (pinfunction "A1_A1") (pintype "passive"))
      (node (ref "J1") (pin "A2") (pinfunction "A2_A2") (pintype "passive"))
      (node (ref "J1") (pin "A3") (pinfunction "A3_A3") (pintype "passive"))
      (node (ref "J1") (pin "A4") (pinfunction "A4_A4") (pintype "passive"))
      (node (ref "J1") (pin "B1") (pinfunction "B1_B1") (pintype "passive"))
      (node (ref "J1") (pin "B2") (pinfunction "B2_B2") (pintype "passive"))
      (node (ref "J1") (pin "B3") (pinfunction "B3_B3") (pintype "passive"))
      (node (ref "J1") (pin "C1") (pinfunction "C1_C1") (pintype "passive"))
      (node (ref "J1") (pin "C2") (pinfunction "C2_C2") (pintype "passive"))
      (node (ref "J1") (pin "C3") (pinfunction "C3_C3") (pintype "passive"))
      (node (ref "J2") (pin "A1") (pinfunction "A1_A1") (pintype "passive"))
      (node (ref "J2") (pin "A2") (pinfunction "A2_A2") (pintype "passive"))
      (node (ref "J2") (pin "A3") (pinfunction "A3_A3") (pintype "passive"))
      (node (ref "J2") (pin "A4") (pinfunction "A4_A4") (pintype "passive"))
      (node (ref "J2") (pin "B1") (pinfunction "B1_B1") (pintype "passive"))
      (node (ref "J2") (pin "B2") (pinfunction "B2_B2") (pintype "passive"))
      (node (ref "J2") (pin "B3") (pinfunction "B3_B3") (pintype "passive"))
      (node (ref "J2") (pin "C1") (pinfunction "C1_C1") (pintype "passive"))
      (node (ref "J2") (pin "C2") (pinfunction "C2_C2") (pintype "passive"))
      (node (ref "J2") (pin "C3") (pinfunction "C3_C3") (pintype "passive"))
      (node (ref "J3") (pin "A1") (pinfunction "A1_A1") (pintype "passive"))
      (node (ref "J3") (pin "A2") (pinfunction "A2_A2") (pintype "passive"))
      (node (ref "J3") (pin "A3") (pinfunction "A3_A3") (pintype "passive"))
      (node (ref "J3") (pin "A4") (pinfunction "A4_A4") (pintype "passive"))
      (node (ref "J3") (pin "B1") (pinfunction "B1_B1") (pintype "passive"))
      (node (ref "J3") (pin "B2") (pinfunction "B2_B2") (pintype "passive"))
      (node (ref "J3") (pin "B3") (pinfunction "B3_B3") (pintype "passive"))
      (node (ref "J3") (pin "C1") (pinfunction "C1_C1") (pintype "passive"))
      (node (ref "J3") (pin "C2") (pinfunction "C2_C2") (pintype "passive"))
      (node (ref "J3") (pin "C3") (pinfunction "C3_C3") (pintype "passive"))
      (node (ref "J4") (pin "A1") (pinfunction "A1_A1") (pintype "passive"))
      (node (ref "J4") (pin "A2") (pinfunction "A2_A2") (pintype "passive"))
      (node (ref "J4") (pin "A3") (pinfunction "A3_A3") (pintype "passive"))
      (node (ref "J4") (pin "A4") (pinfunction "A4_A4") (pintype "passive"))
      (node (ref "J4") (pin "B1") (pinfunction "B1_B1") (pintype "passive"))
      (node (ref "J4") (pin "B2") (pinfunction "B2_B2") (pintype "passive"))
      (node (ref "J4") (pin "B3") (pinfunction "B3_B3") (pintype "passive"))
      (node (ref "J4") (pin "C1") (pinfunction "C1_C1") (pintype "passive"))
      (node (ref "J4") (pin "C2") (pinfunction "C2_C2") (pintype "passive"))
      (node (ref "J4") (pin "C3") (pinfunction "C3_C3") (pintype "passive"))
      (node (ref "J5") (pin "A1") (pinfunction "A1_A1") (pintype "passive"))
      (node (ref "J5") (pin "A2") (pinfunction "A2_A2") (pintype "passive"))
      (node (ref "J5") (pin "A3") (pinfunction "A3_A3") (pintype "passive"))
      (node (ref "J5") (pin "A4") (pinfunction "A4_A4") (pintype "passive"))
      (node (ref "J5") (pin "B1") (pinfunction "B1_B1") (pintype "passive"))
      (node (ref "J5") (pin "B2") (pinfunction "B2_B2") (pintype "passive"))
      (node (ref "J5") (pin "B3") (pinfunction "B3_B3") (pintype "passive"))
      (node (ref "J5") (pin "C1") (pinfunction "C1_C1") (pintype "passive"))
      (node (ref "J5") (pin "C2") (pinfunction "C2_C2") (pintype "passive"))
      (node (ref "J5") (pin "C3") (pinfunction "C3_C3") (pintype "passive"))
      (node (ref "J6") (pin "A1") (pinfunction "A1_A1") (pintype "passive"))
      (node (ref "J6") (pin "A2") (pinfunction "A2_A2") (pintype "passive"))
      (node (ref "J6") (pin "A3") (pinfunction "A3_A3") (pintype "passive"))
      (node (ref "J6") (pin "A4") (pinfunction "A4_A4") (pintype "passive"))
      (node (ref "J6") (pin "B1") (pinfunction "B1_B1") (pintype "passive"))
      (node (ref "J6") (pin "B2") (pinfunction "B2_B2") (pintype "passive"))
      (node (ref "J6") (pin "B3") (pinfunction "B3_B3") (pintype "passive"))
      (node (ref "J6") (pin "C1") (pinfunction "C1_C1") (pintype "passive"))
      (node (ref "J6") (pin "C2") (pinfunction "C2_C2") (pintype "passive"))
      (node (ref "J6") (pin "C3") (pinfunction "C3_C3") (pintype "passive"))
      (node (ref "J7") (pin "A1") (pinfunction "A1_A1") (pintype "passive"))
      (node (ref "J7") (pin "A2") (pinfunction "A2_A2") (pintype "passive"))
      (node (ref "J7") (pin "A3") (pinfunction "A3_A3") (pintype "passive"))
      (node (ref "J7") (pin "A4") (pinfunction "A4_A4") (pintype "passive"))
      (node (ref "J7") (pin "B1") (pinfunction "B1_B1") (pintype "passive"))
      (node (ref "J7") (pin "B2") (pinfunction "B2_B2") (pintype "passive"))
      (node (ref "J7") (pin "B3") (pinfunction "B3_B3") (pintype "passive"))
      (node (ref "J7") (pin "C1") (pinfunction "C1_C1") (pintype "passive"))
      (node (ref "J7") (pin "C2") (pinfunction "C2_C2") (pintype "passive"))
      (node (ref "J7") (pin "C3") (pinfunction "C3_C3") (pintype "passive"))
      (node (ref "J8") (pin "A1") (pinfunction "A1_A1") (pintype "passive"))
      (node (ref "J8") (pin "A2") (pinfunction "A2_A2") (pintype "passive"))
      (node (ref "J8") (pin "A3") (pinfunction "A3_A3") (pintype "passive"))
      (node (ref "J8") (pin "A4") (pinfunction "A4_A4") (pintype "passive"))
      (node (ref "J8") (pin "B1") (pinfunction "B1_B1") (pintype "passive"))
      (node (ref "J8") (pin "B2") (pinfunction "B2_B2") (pintype "passive"))
      (node (ref "J8") (pin "B3") (pinfunction "B3_B3") (pintype "passive"))
      (node (ref "J8") (pin "C1") (pinfunction "C1_C1") (pintype "passive"))
      (node (ref "J8") (pin "C2") (pinfunction "C2_C2") (pintype "passive"))
      (node (ref "J8") (pin "C3") (pinfunction "C3_C3") (pintype "passive"))
      (node (ref "JP2") (pin "1") (pinfunction "1_1") (pintype "passive"))
      (node (ref "U1") (pin "1") (pinfunction "ADJ/GND_1") (pintype "passive"))
      (node (ref "U2") (pin "1") (pinfunction "ADJ/GND_1") (pintype "passive"))
      (node (ref "XS1") (pin "1") (pinfunction "P$1_1") (pintype "bidirectional"))
    )
    (net (code "32") (name "Net-(U1-IN)") (class "Default")
      (node (ref "C1") (pin "+") (pinfunction "+_+") (pintype "passive"))
      (node (ref "U1") (pin "3") (pinfunction "IN_3") (pintype "power_in"))
    )
    (net (code "33") (name "Net-(U2-IN)") (class "Default")
      (node (ref "C3") (pin "+") (pinfunction "+_+") (pintype "passive"))
      (node (ref "U2") (pin "3") (pinfunction "IN_3") (pintype "power_in"))
    )
  )
)
